# microcontroller.net
KiCad netlist of a schematic drawn in Altium Designer
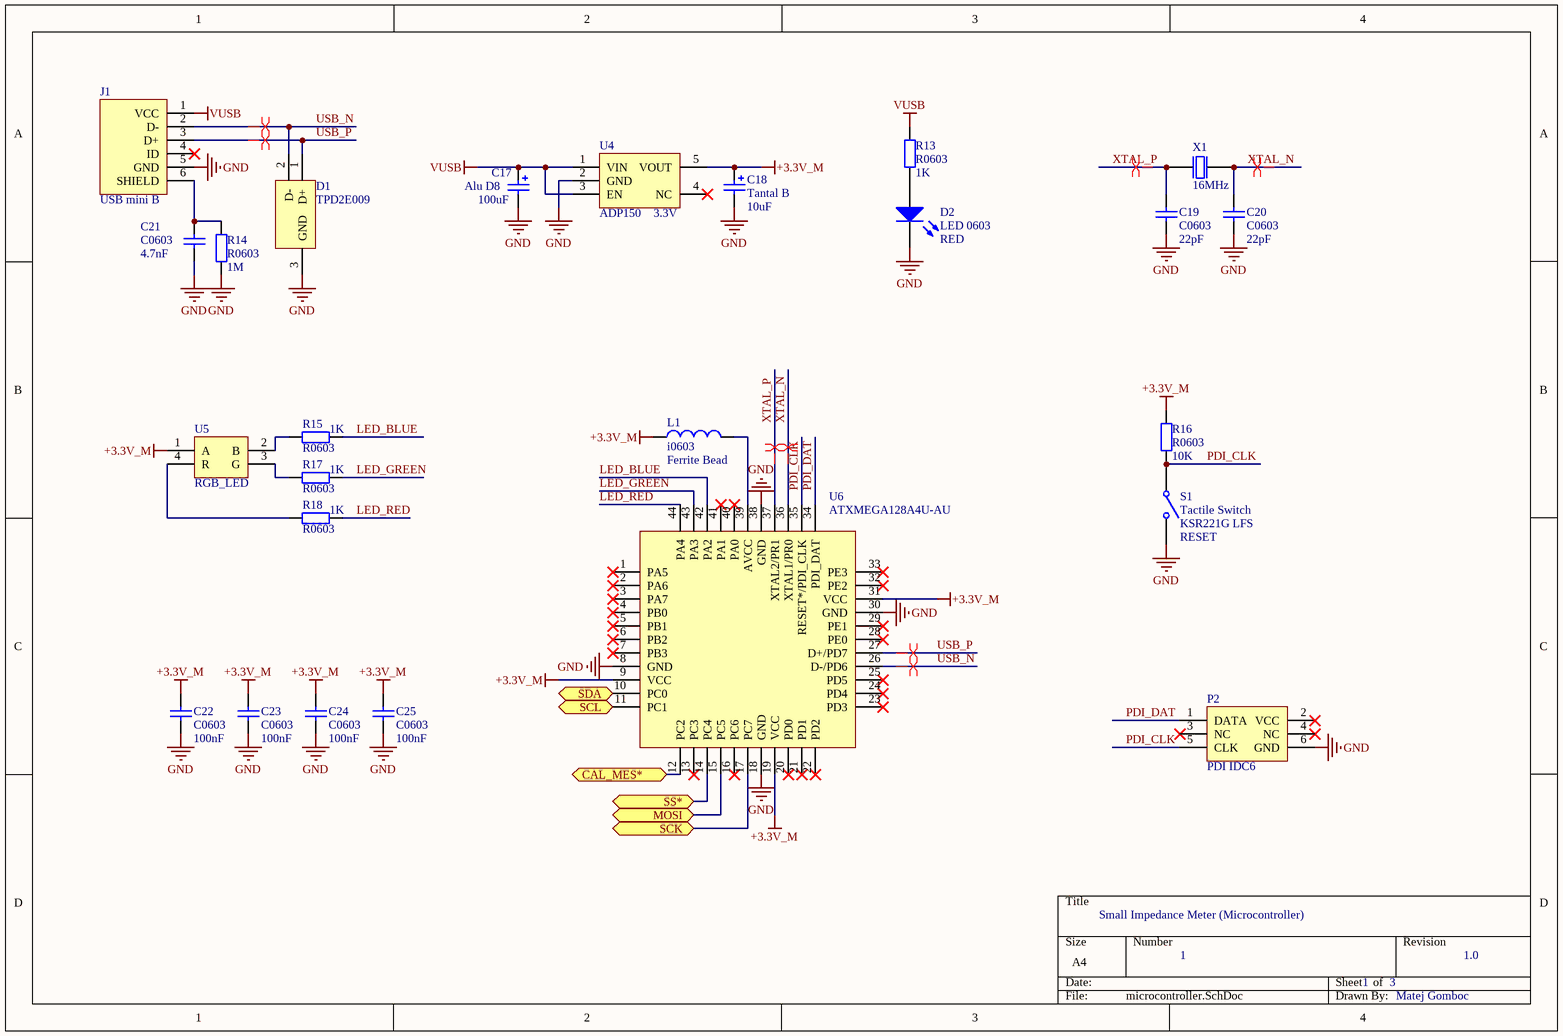
[diagram p0: microcontroller.SchDoc]

(export (version "E")
  (design (tool "Eeschema 10.0.6"))
  (components
    (comp (ref "C17")
      (value "Alu D8")
      (footprint "PANASONIC SIZE D8")
      (description "Aluminium Electrolythic Capacitor")
      (fields (field (name "ALTIUM_VALUE") "100uF"))
      (libsource (lib "LSP_Schlib") (part "Capacitor Aluminium"))
    )
    (comp (ref "C18")
      (value "Tantal B")
      (footprint "AVX-CAPC3528_V")
      (description "Tantalum Capacitor")
      (fields (field (name "ALTIUM_VALUE") "10uF"))
      (libsource (lib "LSP_Schlib") (part "Capacitor Tantalum"))
    )
    (comp (ref "C19")
      (value "C0603")
      (footprint "0603_HandSoldering")
      (description "Ceramic Capacitor")
      (fields (field (name "ALTIUM_VALUE") "22pF"))
      (libsource (lib "LSP_Schlib") (part "Capacitor"))
    )
    (comp (ref "C20")
      (value "C0603")
      (footprint "0603_HandSoldering")
      (description "Ceramic Capacitor")
      (fields (field (name "ALTIUM_VALUE") "22pF"))
      (libsource (lib "LSP_Schlib") (part "Capacitor"))
    )
    (comp (ref "C21")
      (value "C0603")
      (footprint "0603_HandSoldering")
      (description "Ceramic Capacitor")
      (fields (field (name "ALTIUM_VALUE") "4.7nF"))
      (libsource (lib "LSP_Schlib") (part "Capacitor"))
    )
    (comp (ref "C22")
      (value "C0603")
      (footprint "0603_HandSoldering")
      (description "Ceramic Capacitor")
      (fields (field (name "ALTIUM_VALUE") "100nF"))
      (libsource (lib "LSP_Schlib") (part "Capacitor"))
    )
    (comp (ref "C23")
      (value "C0603")
      (footprint "0603_HandSoldering")
      (description "Ceramic Capacitor")
      (fields (field (name "ALTIUM_VALUE") "100nF"))
      (libsource (lib "LSP_Schlib") (part "Capacitor"))
    )
    (comp (ref "C24")
      (value "C0603")
      (footprint "0603_HandSoldering")
      (description "Ceramic Capacitor")
      (fields (field (name "ALTIUM_VALUE") "100nF"))
      (libsource (lib "LSP_Schlib") (part "Capacitor"))
    )
    (comp (ref "C25")
      (value "C0603")
      (footprint "0603_HandSoldering")
      (description "Ceramic Capacitor")
      (fields (field (name "ALTIUM_VALUE") "100nF"))
      (libsource (lib "LSP_Schlib") (part "Capacitor"))
    )
    (comp (ref "D1")
      (value "TPD2E009")
      (footprint "TPD2E009_SOT23_3")
      (description "ESD protection")
      (libsource (lib "LSP_Schlib") (part "TPD2E009"))
    )
    (comp (ref "D2")
      (value "LED 0603")
      (footprint "0603_LED")
      (description "SMD LED 0603")
      (fields (field (name "ALTIUM_VALUE") "RED"))
      (libsource (lib "LSP_Schlib") (part "LED"))
    )
    (comp (ref "J1")
      (value "USB mini B")
      (footprint "USB mini B receptacle")
      (description "USB 2.0 mini B receptacle")
      (libsource (lib "LSP_Schlib") (part "USB_mini_B"))
    )
    (comp (ref "L1")
      (value "i0603")
      (footprint "0603_HandSoldering")
      (description "Inductor")
      (fields (field (name "ALTIUM_VALUE") "Ferrite Bead"))
      (libsource (lib "LSP_Schlib") (part "Inductor"))
    )
    (comp (ref "P2")
      (value "PDI IDC6")
      (footprint "PDI_HDR2X3")
      (description "PDI Programming Interface")
      (libsource (lib "LSP_Schlib") (part "PDI_Header"))
    )
    (comp (ref "R13")
      (value "R0603")
      (footprint "0603_HandSoldering")
      (description "Resistor")
      (fields (field (name "ALTIUM_VALUE") "1K"))
      (libsource (lib "") (part "Resistor_3"))
    )
    (comp (ref "R14")
      (value "R0603")
      (footprint "0603_HandSoldering")
      (description "Resistor")
      (fields (field (name "ALTIUM_VALUE") "1M"))
      (libsource (lib "LSP_Schlib") (part "Resistor"))
    )
    (comp (ref "R15")
      (value "R0603")
      (footprint "0603_HandSoldering")
      (description "Resistor")
      (fields (field (name "ALTIUM_VALUE") "1K"))
      (libsource (lib "") (part "Resistor_1"))
    )
    (comp (ref "R16")
      (value "R0603")
      (footprint "0603_HandSoldering")
      (description "Resistor")
      (fields (field (name "ALTIUM_VALUE") "10K"))
      (libsource (lib "LSP_Schlib") (part "Resistor"))
    )
    (comp (ref "R17")
      (value "R0603")
      (footprint "0603_HandSoldering")
      (description "Resistor")
      (fields (field (name "ALTIUM_VALUE") "1K"))
      (libsource (lib "") (part "Resistor_2"))
    )
    (comp (ref "R18")
      (value "R0603")
      (footprint "0603_HandSoldering")
      (description "Resistor")
      (fields (field (name "ALTIUM_VALUE") "1K"))
      (libsource (lib "") (part "Resistor_2"))
    )
    (comp (ref "S1")
      (value "Tactile Switch")
      (footprint "KSR221G_LFS_Tactile_Switch")
      (description "KSR221G LFS Tactile Switch")
      (fields (field (name "ALTIUM_VALUE") "KSR221G LFS") (field (name "NOTE") "RESET"))
      (libsource (lib "LSP_Schlib") (part "SW-SPST"))
    )
    (comp (ref "U4")
      (value "ADP150")
      (footprint "ADP150")
      (description "100 mA Voltage Regulator")
      (fields (field (name "ALTIUM_VALUE") "3.3V"))
      (libsource (lib "LSP_Schlib") (part "ADP150"))
    )
    (comp (ref "U5")
      (value "RGB_LED")
      (footprint "PLCC-4_LED")
      (description "RGB LED ASMB-MTB0-0A3A2")
      (libsource (lib "LSP_Schlib") (part "RGB_LED"))
    )
    (comp (ref "U6")
      (value "ATXMEGA128A4U-AU")
      (footprint "ATXMEGAA4U_TQFP44")
      (description "8/16-bit Atmel XMEGA Microcontroller")
      (libsource (lib "LSP_Schlib") (part "ATXMEGA128A4U-AU"))
    )
    (comp (ref "X1")
      (value "16MHz")
      (footprint "XTAL_TH_LOW")
      (description "XTAL TH Low Profile")
      (libsource (lib "LSP_Schlib") (part "XTAL_TH_LOW"))
    )
  )
  (nets
    (net (code "1") (name "+3.3V_M") (class "Default")
      (node (ref "C18") (pin "1") (pinfunction "1_1") (pintype "passive"))
      (node (ref "C22") (pin "1") (pinfunction "1_1") (pintype "passive"))
      (node (ref "C23") (pin "1") (pinfunction "1_1") (pintype "passive"))
      (node (ref "C24") (pin "1") (pinfunction "1_1") (pintype "passive"))
      (node (ref "C25") (pin "1") (pinfunction "1_1") (pintype "passive"))
      (node (ref "L1") (pin "1") (pinfunction "1_1") (pintype "passive"))
      (node (ref "R16") (pin "2") (pinfunction "2_2") (pintype "passive"))
      (node (ref "U4") (pin "5") (pinfunction "VOUT_5") (pintype "passive"))
      (node (ref "U5") (pin "1") (pinfunction "A_1") (pintype "passive"))
      (node (ref "U6") (pin "19") (pinfunction "VCC_19") (pintype "passive"))
      (node (ref "U6") (pin "31") (pinfunction "VCC_31") (pintype "passive"))
      (node (ref "U6") (pin "9") (pinfunction "VCC_9") (pintype "passive"))
    )
    (net (code "2") (name "/CAL_MES*") (class "Default")
      (node (ref "U6") (pin "12") (pinfunction "PC2_12") (pintype "passive"))
    )
    (net (code "3") (name "/LED_BLUE") (class "Default")
      (node (ref "R15") (pin "2") (pinfunction "2_2") (pintype "passive"))
      (node (ref "U6") (pin "42") (pinfunction "PA2_42") (pintype "passive"))
    )
    (net (code "4") (name "/LED_GREEN") (class "Default")
      (node (ref "R17") (pin "1") (pinfunction "1_1") (pintype "passive"))
      (node (ref "U6") (pin "43") (pinfunction "PA3_43") (pintype "passive"))
    )
    (net (code "5") (name "/LED_RED") (class "Default")
      (node (ref "R18") (pin "1") (pinfunction "1_1") (pintype "passive"))
      (node (ref "U6") (pin "44") (pinfunction "PA4_44") (pintype "passive"))
    )
    (net (code "6") (name "/MOSI") (class "Default")
      (node (ref "U6") (pin "15") (pinfunction "PC5_15") (pintype "passive"))
    )
    (net (code "7") (name "/PDI_CLK") (class "Default")
      (node (ref "P2") (pin "5") (pinfunction "CLK_5") (pintype "passive"))
      (node (ref "R16") (pin "1") (pinfunction "1_1") (pintype "passive"))
      (node (ref "S1") (pin "1") (pinfunction "COMMON_1") (pintype "passive"))
      (node (ref "U6") (pin "35") (pinfunction "RESET*/PDI_CLK_35") (pintype "passive"))
    )
    (net (code "8") (name "/PDI_DAT") (class "Default")
      (node (ref "P2") (pin "1") (pinfunction "DATA_1") (pintype "passive"))
      (node (ref "U6") (pin "34") (pinfunction "PDI_DAT_34") (pintype "passive"))
    )
    (net (code "9") (name "/SCK") (class "Default")
      (node (ref "U6") (pin "17") (pinfunction "PC7_17") (pintype "passive"))
    )
    (net (code "10") (name "/SCL") (class "Default")
      (node (ref "U6") (pin "11") (pinfunction "PC1_11") (pintype "passive"))
    )
    (net (code "11") (name "/SDA") (class "Default")
      (node (ref "U6") (pin "10") (pinfunction "PC0_10") (pintype "passive"))
    )
    (net (code "12") (name "/SS*") (class "Default")
      (node (ref "U6") (pin "14") (pinfunction "PC4_14") (pintype "passive"))
    )
    (net (code "13") (name "/USB_N") (class "Default")
      (node (ref "D1") (pin "2") (pinfunction "D-_2") (pintype "passive"))
      (node (ref "J1") (pin "2") (pinfunction "D-_2") (pintype "passive"))
      (node (ref "U6") (pin "26") (pinfunction "D-/PD6_26") (pintype "passive"))
    )
    (net (code "14") (name "/USB_P") (class "Default")
      (node (ref "D1") (pin "1") (pinfunction "D+_1") (pintype "passive"))
      (node (ref "J1") (pin "3") (pinfunction "D+_3") (pintype "passive"))
      (node (ref "U6") (pin "27") (pinfunction "D+/PD7_27") (pintype "passive"))
    )
    (net (code "15") (name "/XTAL_N") (class "Default")
      (node (ref "C20") (pin "2") (pinfunction "2_2") (pintype "passive"))
      (node (ref "U6") (pin "36") (pinfunction "XTAL1/PR0_36") (pintype "passive"))
      (node (ref "X1") (pin "2") (pinfunction "out_2") (pintype "passive"))
    )
    (net (code "16") (name "/XTAL_P") (class "Default")
      (node (ref "C19") (pin "2") (pinfunction "2_2") (pintype "passive"))
      (node (ref "U6") (pin "37") (pinfunction "XTAL2/PR1_37") (pintype "passive"))
      (node (ref "X1") (pin "1") (pinfunction "inp_1") (pintype "passive"))
    )
    (net (code "17") (name "GND") (class "Default")
      (node (ref "C17") (pin "2") (pinfunction "2_2") (pintype "passive"))
      (node (ref "C18") (pin "2") (pinfunction "2_2") (pintype "passive"))
      (node (ref "C19") (pin "1") (pinfunction "1_1") (pintype "passive"))
      (node (ref "C20") (pin "1") (pinfunction "1_1") (pintype "passive"))
      (node (ref "C21") (pin "1") (pinfunction "1_1") (pintype "passive"))
      (node (ref "C22") (pin "2") (pinfunction "2_2") (pintype "passive"))
      (node (ref "C23") (pin "2") (pinfunction "2_2") (pintype "passive"))
      (node (ref "C24") (pin "2") (pinfunction "2_2") (pintype "passive"))
      (node (ref "C25") (pin "2") (pinfunction "2_2") (pintype "passive"))
      (node (ref "D1") (pin "3") (pinfunction "GND_3") (pintype "passive"))
      (node (ref "D2") (pin "2") (pinfunction "K_2") (pintype "passive"))
      (node (ref "J1") (pin "5") (pinfunction "GND_5") (pintype "passive"))
      (node (ref "P2") (pin "6") (pinfunction "GND_6") (pintype "passive"))
      (node (ref "R14") (pin "1") (pinfunction "1_1") (pintype "passive"))
      (node (ref "S1") (pin "2") (pinfunction "NO_2") (pintype "passive"))
      (node (ref "U4") (pin "2") (pinfunction "GND_2") (pintype "passive"))
      (node (ref "U6") (pin "18") (pinfunction "GND_18") (pintype "passive"))
      (node (ref "U6") (pin "30") (pinfunction "GND_30") (pintype "passive"))
      (node (ref "U6") (pin "38") (pinfunction "GND_38") (pintype "passive"))
      (node (ref "U6") (pin "8") (pinfunction "GND_8") (pintype "passive"))
    )
    (net (code "18") (name "Net-(D2-A)") (class "Default")
      (node (ref "D2") (pin "1") (pinfunction "A_1") (pintype "passive"))
      (node (ref "R13") (pin "2") (pinfunction "2_2") (pintype "passive"))
    )
    (net (code "19") (name "Net-(J1-SHIELD)") (class "Default")
      (node (ref "C21") (pin "2") (pinfunction "2_2") (pintype "passive"))
      (node (ref "J1") (pin "6") (pinfunction "SHIELD_6") (pintype "passive"))
      (node (ref "R14") (pin "2") (pinfunction "2_2") (pintype "passive"))
    )
    (net (code "20") (name "Net-(U5-B)") (class "Default")
      (node (ref "R15") (pin "1") (pinfunction "1_1") (pintype "passive"))
      (node (ref "U5") (pin "2") (pinfunction "B_2") (pintype "passive"))
    )
    (net (code "21") (name "Net-(U5-G)") (class "Default")
      (node (ref "R17") (pin "2") (pinfunction "2_2") (pintype "passive"))
      (node (ref "U5") (pin "3") (pinfunction "G_3") (pintype "passive"))
    )
    (net (code "22") (name "Net-(U5-R)") (class "Default")
      (node (ref "R18") (pin "2") (pinfunction "2_2") (pintype "passive"))
      (node (ref "U5") (pin "4") (pinfunction "R_4") (pintype "passive"))
    )
    (net (code "23") (name "Net-(U6-AVCC)") (class "Default")
      (node (ref "L1") (pin "2") (pinfunction "2_2") (pintype "passive"))
      (node (ref "U6") (pin "39") (pinfunction "AVCC_39") (pintype "passive"))
    )
    (net (code "24") (name "VUSB") (class "Default")
      (node (ref "C17") (pin "1") (pinfunction "1_1") (pintype "passive"))
      (node (ref "J1") (pin "1") (pinfunction "VCC_1") (pintype "passive"))
      (node (ref "R13") (pin "1") (pinfunction "1_1") (pintype "passive"))
      (node (ref "U4") (pin "1") (pinfunction "VIN_1") (pintype "passive"))
      (node (ref "U4") (pin "3") (pinfunction "EN_3") (pintype "passive"))
    )
    (net (code "25") (name "unconnected-(J1-ID-Pad4)") (class "Default")
      (node (ref "J1") (pin "4") (pinfunction "ID_4") (pintype "passive+no_connect"))
    )
    (net (code "26") (name "unconnected-(P2-NC-Pad3)") (class "Default")
      (node (ref "P2") (pin "3") (pinfunction "NC_3") (pintype "passive+no_connect"))
    )
    (net (code "27") (name "unconnected-(P2-NC-Pad4)") (class "Default")
      (node (ref "P2") (pin "4") (pinfunction "NC_4") (pintype "passive+no_connect"))
    )
    (net (code "28") (name "unconnected-(P2-VCC-Pad2)") (class "Default")
      (node (ref "P2") (pin "2") (pinfunction "VCC_2") (pintype "passive+no_connect"))
    )
    (net (code "29") (name "unconnected-(U4-NC-Pad4)") (class "Default")
      (node (ref "U4") (pin "4") (pinfunction "NC_4") (pintype "passive+no_connect"))
    )
    (net (code "30") (name "unconnected-(U6-PA0-Pad40)") (class "Default")
      (node (ref "U6") (pin "40") (pinfunction "PA0_40") (pintype "passive+no_connect"))
    )
    (net (code "31") (name "unconnected-(U6-PA1-Pad41)") (class "Default")
      (node (ref "U6") (pin "41") (pinfunction "PA1_41") (pintype "passive+no_connect"))
    )
    (net (code "32") (name "unconnected-(U6-PA5-Pad1)") (class "Default")
      (node (ref "U6") (pin "1") (pinfunction "PA5_1") (pintype "passive+no_connect"))
    )
    (net (code "33") (name "unconnected-(U6-PA6-Pad2)") (class "Default")
      (node (ref "U6") (pin "2") (pinfunction "PA6_2") (pintype "passive+no_connect"))
    )
    (net (code "34") (name "unconnected-(U6-PA7-Pad3)") (class "Default")
      (node (ref "U6") (pin "3") (pinfunction "PA7_3") (pintype "passive+no_connect"))
    )
    (net (code "35") (name "unconnected-(U6-PB0-Pad4)") (class "Default")
      (node (ref "U6") (pin "4") (pinfunction "PB0_4") (pintype "passive+no_connect"))
    )
    (net (code "36") (name "unconnected-(U6-PB1-Pad5)") (class "Default")
      (node (ref "U6") (pin "5") (pinfunction "PB1_5") (pintype "passive+no_connect"))
    )
    (net (code "37") (name "unconnected-(U6-PB2-Pad6)") (class "Default")
      (node (ref "U6") (pin "6") (pinfunction "PB2_6") (pintype "passive+no_connect"))
    )
    (net (code "38") (name "unconnected-(U6-PB3-Pad7)") (class "Default")
      (node (ref "U6") (pin "7") (pinfunction "PB3_7") (pintype "passive+no_connect"))
    )
    (net (code "39") (name "unconnected-(U6-PC3-Pad13)") (class "Default")
      (node (ref "U6") (pin "13") (pinfunction "PC3_13") (pintype "passive+no_connect"))
    )
    (net (code "40") (name "unconnected-(U6-PC6-Pad16)") (class "Default")
      (node (ref "U6") (pin "16") (pinfunction "PC6_16") (pintype "passive+no_connect"))
    )
    (net (code "41") (name "unconnected-(U6-PD0-Pad20)") (class "Default")
      (node (ref "U6") (pin "20") (pinfunction "PD0_20") (pintype "passive+no_connect"))
    )
    (net (code "42") (name "unconnected-(U6-PD1-Pad21)") (class "Default")
      (node (ref "U6") (pin "21") (pinfunction "PD1_21") (pintype "passive+no_connect"))
    )
    (net (code "43") (name "unconnected-(U6-PD2-Pad22)") (class "Default")
      (node (ref "U6") (pin "22") (pinfunction "PD2_22") (pintype "passive+no_connect"))
    )
    (net (code "44") (name "unconnected-(U6-PD3-Pad23)") (class "Default")
      (node (ref "U6") (pin "23") (pinfunction "PD3_23") (pintype "passive+no_connect"))
    )
    (net (code "45") (name "unconnected-(U6-PD4-Pad24)") (class "Default")
      (node (ref "U6") (pin "24") (pinfunction "PD4_24") (pintype "passive+no_connect"))
    )
    (net (code "46") (name "unconnected-(U6-PD5-Pad25)") (class "Default")
      (node (ref "U6") (pin "25") (pinfunction "PD5_25") (pintype "passive+no_connect"))
    )
    (net (code "47") (name "unconnected-(U6-PE0-Pad28)") (class "Default")
      (node (ref "U6") (pin "28") (pinfunction "PE0_28") (pintype "passive+no_connect"))
    )
    (net (code "48") (name "unconnected-(U6-PE1-Pad29)") (class "Default")
      (node (ref "U6") (pin "29") (pinfunction "PE1_29") (pintype "passive+no_connect"))
    )
    (net (code "49") (name "unconnected-(U6-PE2-Pad32)") (class "Default")
      (node (ref "U6") (pin "32") (pinfunction "PE2_32") (pintype "passive+no_connect"))
    )
    (net (code "50") (name "unconnected-(U6-PE3-Pad33)") (class "Default")
      (node (ref "U6") (pin "33") (pinfunction "PE3_33") (pintype "passive+no_connect"))
    )
  )
)
